# ATTEN_v2.net
KiCad netlist of a schematic drawn in EAGLE
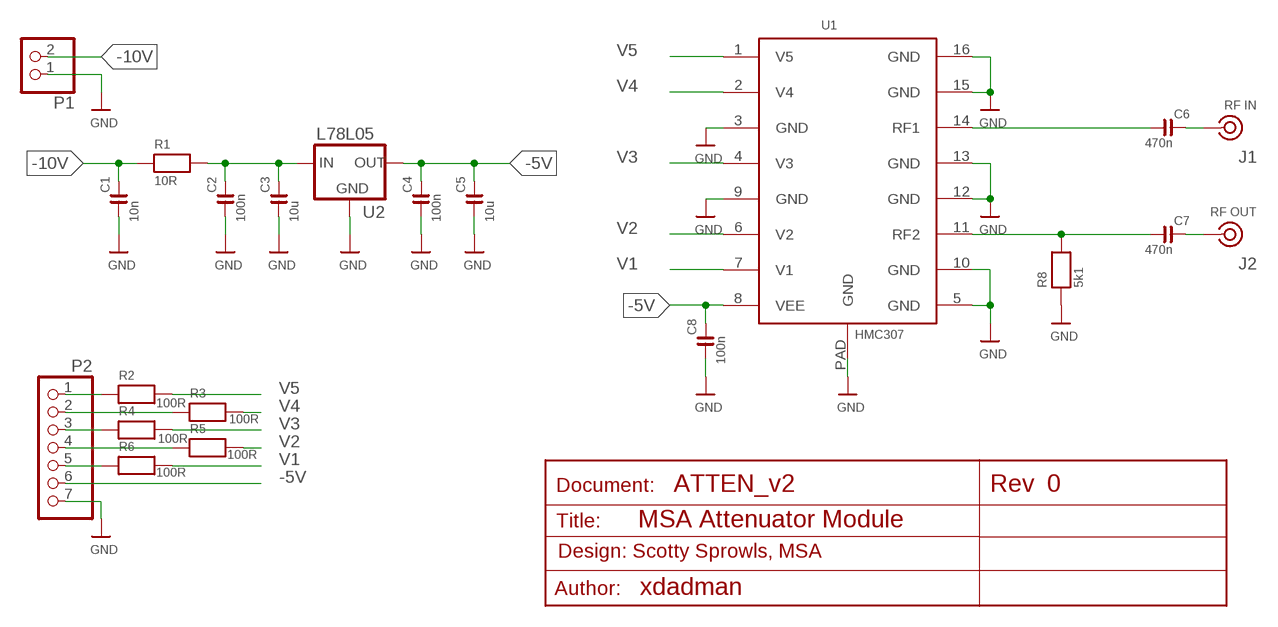
[diagram p0: schematic, sheet 1]

(export (version "E")
  (design (tool "Eeschema 10.0.6"))
  (components
    (comp (ref "C1")
      (value "10n")
      (footprint "eagle-import:C0805")
      (libsource (lib "eagle-import") (part "C080510N"))
    )
    (comp (ref "C2")
      (value "100n")
      (footprint "eagle-import:C0805")
      (libsource (lib "eagle-import") (part "C0805100N"))
    )
    (comp (ref "C3")
      (value "10u")
      (footprint "eagle-import:1206")
      (libsource (lib "eagle-import") (part "CC120610U"))
    )
    (comp (ref "C4")
      (value "100n")
      (footprint "eagle-import:C0805")
      (libsource (lib "eagle-import") (part "C0805100N"))
    )
    (comp (ref "C5")
      (value "10u")
      (footprint "eagle-import:1206")
      (libsource (lib "eagle-import") (part "CC120610U"))
    )
    (comp (ref "C6")
      (value "470n")
      (footprint "eagle-import:C0805")
      (libsource (lib "eagle-import") (part "C0805470N"))
    )
    (comp (ref "C7")
      (value "470n")
      (footprint "eagle-import:C0805")
      (libsource (lib "eagle-import") (part "C0805470N"))
    )
    (comp (ref "C8")
      (value "100n")
      (footprint "eagle-import:C0805")
      (libsource (lib "eagle-import") (part "C0805100N"))
    )
    (comp (ref "J1")
      (value "RF IN")
      (footprint "eagle-import:SLIM_COAX_PAD")
      (libsource (lib "eagle-import") (part "COAX"))
    )
    (comp (ref "J2")
      (value "RF OUT")
      (footprint "eagle-import:SLIM_COAX_PAD")
      (libsource (lib "eagle-import") (part "COAX"))
    )
    (comp (ref "P1")
      (value "PINHD-1X2")
      (footprint "eagle-import:1X02")
      (libsource (lib "eagle-import") (part "PINHD-1X2"))
    )
    (comp (ref "P2")
      (value "PINHD-1X7")
      (footprint "eagle-import:1X07")
      (libsource (lib "eagle-import") (part "PINHD-1X7"))
    )
    (comp (ref "R1")
      (value "10R")
      (footprint "eagle-import:R0805")
      (libsource (lib "eagle-import") (part "R080510R"))
    )
    (comp (ref "R2")
      (value "100R")
      (footprint "eagle-import:R0402")
      (libsource (lib "eagle-import") (part "R0402100R"))
    )
    (comp (ref "R3")
      (value "100R")
      (footprint "eagle-import:R0402")
      (libsource (lib "eagle-import") (part "R0402100R"))
    )
    (comp (ref "R4")
      (value "100R")
      (footprint "eagle-import:R0402")
      (libsource (lib "eagle-import") (part "R0402100R"))
    )
    (comp (ref "R5")
      (value "100R")
      (footprint "eagle-import:R0402")
      (libsource (lib "eagle-import") (part "R0402100R"))
    )
    (comp (ref "R6")
      (value "100R")
      (footprint "eagle-import:R0402")
      (libsource (lib "eagle-import") (part "R0402100R"))
    )
    (comp (ref "R8")
      (value "5k1")
      (footprint "eagle-import:R0402")
      (libsource (lib "eagle-import") (part "R04025K1"))
    )
    (comp (ref "U1")
      (value "HMC307")
      (footprint "eagle-import:QSOP16_PAD")
      (libsource (lib "eagle-import") (part "HMC307"))
    )
    (comp (ref "U2")
      (value "L78L05")
      (footprint "eagle-import:SOT89")
      (libsource (lib "eagle-import") (part "L78L05"))
    )
  )
  (nets
    (net (code "1") (name "-5V") (class "Default")
      (node (ref "C4") (pin "2") (pinfunction "2_2") (pintype "passive"))
      (node (ref "C5") (pin "2") (pinfunction "2_2") (pintype "passive"))
      (node (ref "C8") (pin "2") (pinfunction "2_2") (pintype "passive"))
      (node (ref "P2") (pin "6") (pinfunction "6_6") (pintype "passive"))
      (node (ref "U1") (pin "8") (pinfunction "VEE_8") (pintype "bidirectional"))
      (node (ref "U2") (pin "3") (pinfunction "OUT_3") (pintype "passive"))
    )
    (net (code "2") (name "-10V") (class "Default")
      (node (ref "C1") (pin "2") (pinfunction "2_2") (pintype "passive"))
      (node (ref "P1") (pin "2") (pinfunction "2_2") (pintype "passive"))
      (node (ref "R1") (pin "1") (pinfunction "1_1") (pintype "passive"))
    )
    (net (code "3") (name "/V1") (class "Default")
      (node (ref "R6") (pin "2") (pinfunction "2_2") (pintype "passive"))
      (node (ref "U1") (pin "7") (pinfunction "V1_7") (pintype "bidirectional"))
    )
    (net (code "4") (name "/V2") (class "Default")
      (node (ref "R5") (pin "2") (pinfunction "2_2") (pintype "passive"))
      (node (ref "U1") (pin "6") (pinfunction "V2_6") (pintype "bidirectional"))
    )
    (net (code "5") (name "/V3") (class "Default")
      (node (ref "R4") (pin "2") (pinfunction "2_2") (pintype "passive"))
      (node (ref "U1") (pin "4") (pinfunction "V3_4") (pintype "bidirectional"))
    )
    (net (code "6") (name "/V4") (class "Default")
      (node (ref "R3") (pin "2") (pinfunction "2_2") (pintype "passive"))
      (node (ref "U1") (pin "2") (pinfunction "V4_2") (pintype "bidirectional"))
    )
    (net (code "7") (name "/V5") (class "Default")
      (node (ref "R2") (pin "2") (pinfunction "2_2") (pintype "passive"))
      (node (ref "U1") (pin "1") (pinfunction "V5_1") (pintype "bidirectional"))
    )
    (net (code "8") (name "GND") (class "Default")
      (node (ref "C1") (pin "1") (pinfunction "1_1") (pintype "passive"))
      (node (ref "C2") (pin "1") (pinfunction "1_1") (pintype "passive"))
      (node (ref "C3") (pin "1") (pinfunction "1_1") (pintype "passive"))
      (node (ref "C4") (pin "1") (pinfunction "1_1") (pintype "passive"))
      (node (ref "C5") (pin "1") (pinfunction "1_1") (pintype "passive"))
      (node (ref "C8") (pin "1") (pinfunction "1_1") (pintype "passive"))
      (node (ref "P1") (pin "1") (pinfunction "1_1") (pintype "passive"))
      (node (ref "P2") (pin "7") (pinfunction "7_7") (pintype "passive"))
      (node (ref "R8") (pin "1") (pinfunction "1_1") (pintype "passive"))
      (node (ref "U1") (pin "10") (pinfunction "GND_10") (pintype "bidirectional"))
      (node (ref "U1") (pin "12") (pinfunction "GND_12") (pintype "bidirectional"))
      (node (ref "U1") (pin "13") (pinfunction "GND_13") (pintype "bidirectional"))
      (node (ref "U1") (pin "15") (pinfunction "GND_15") (pintype "bidirectional"))
      (node (ref "U1") (pin "16") (pinfunction "GND_16") (pintype "bidirectional"))
      (node (ref "U1") (pin "3") (pinfunction "GND_3") (pintype "bidirectional"))
      (node (ref "U1") (pin "5") (pinfunction "GND_5") (pintype "bidirectional"))
      (node (ref "U1") (pin "9") (pinfunction "GND_9") (pintype "bidirectional"))
      (node (ref "U1") (pin "PAD") (pinfunction "GND_PAD") (pintype "bidirectional"))
      (node (ref "U2") (pin "1") (pinfunction "GND_1") (pintype "input"))
    )
    (net (code "9") (name "Net-(C2-Pad2)") (class "Default")
      (node (ref "C2") (pin "2") (pinfunction "2_2") (pintype "passive"))
      (node (ref "C3") (pin "2") (pinfunction "2_2") (pintype "passive"))
      (node (ref "R1") (pin "2") (pinfunction "2_2") (pintype "passive"))
      (node (ref "U2") (pin "2") (pinfunction "IN_2") (pintype "input"))
      (node (ref "U2") (pin "4") (pinfunction "IN_4") (pintype "input"))
    )
    (net (code "10") (name "Net-(J1A-1)") (class "Default")
      (node (ref "C6") (pin "2") (pinfunction "2_2") (pintype "passive"))
      (node (ref "J1") (pin "SIG") (pinfunction "1_SIG") (pintype "passive"))
    )
    (net (code "11") (name "Net-(J2A-1)") (class "Default")
      (node (ref "C7") (pin "2") (pinfunction "2_2") (pintype "passive"))
      (node (ref "J2") (pin "SIG") (pinfunction "1_SIG") (pintype "passive"))
    )
    (net (code "12") (name "Net-(P2-Pad1)") (class "Default")
      (node (ref "P2") (pin "1") (pinfunction "1_1") (pintype "passive"))
      (node (ref "R2") (pin "1") (pinfunction "1_1") (pintype "passive"))
    )
    (net (code "13") (name "Net-(P2-Pad2)") (class "Default")
      (node (ref "P2") (pin "2") (pinfunction "2_2") (pintype "passive"))
      (node (ref "R3") (pin "1") (pinfunction "1_1") (pintype "passive"))
    )
    (net (code "14") (name "Net-(P2-Pad3)") (class "Default")
      (node (ref "P2") (pin "3") (pinfunction "3_3") (pintype "passive"))
      (node (ref "R4") (pin "1") (pinfunction "1_1") (pintype "passive"))
    )
    (net (code "15") (name "Net-(P2-Pad4)") (class "Default")
      (node (ref "P2") (pin "4") (pinfunction "4_4") (pintype "passive"))
      (node (ref "R5") (pin "1") (pinfunction "1_1") (pintype "passive"))
    )
    (net (code "16") (name "Net-(P2-Pad5)") (class "Default")
      (node (ref "P2") (pin "5") (pinfunction "5_5") (pintype "passive"))
      (node (ref "R6") (pin "1") (pinfunction "1_1") (pintype "passive"))
    )
    (net (code "17") (name "Net-(U1-RF1)") (class "Default")
      (node (ref "C6") (pin "1") (pinfunction "1_1") (pintype "passive"))
      (node (ref "U1") (pin "14") (pinfunction "RF1_14") (pintype "bidirectional"))
    )
    (net (code "18") (name "Net-(U1-RF2)") (class "Default")
      (node (ref "C7") (pin "1") (pinfunction "1_1") (pintype "passive"))
      (node (ref "R8") (pin "2") (pinfunction "2_2") (pintype "passive"))
      (node (ref "U1") (pin "11") (pinfunction "RF2_11") (pintype "bidirectional"))
    )
  )
)
